# LipSync_Pressure_Board.net
KiCad netlist of a schematic drawn in EAGLE
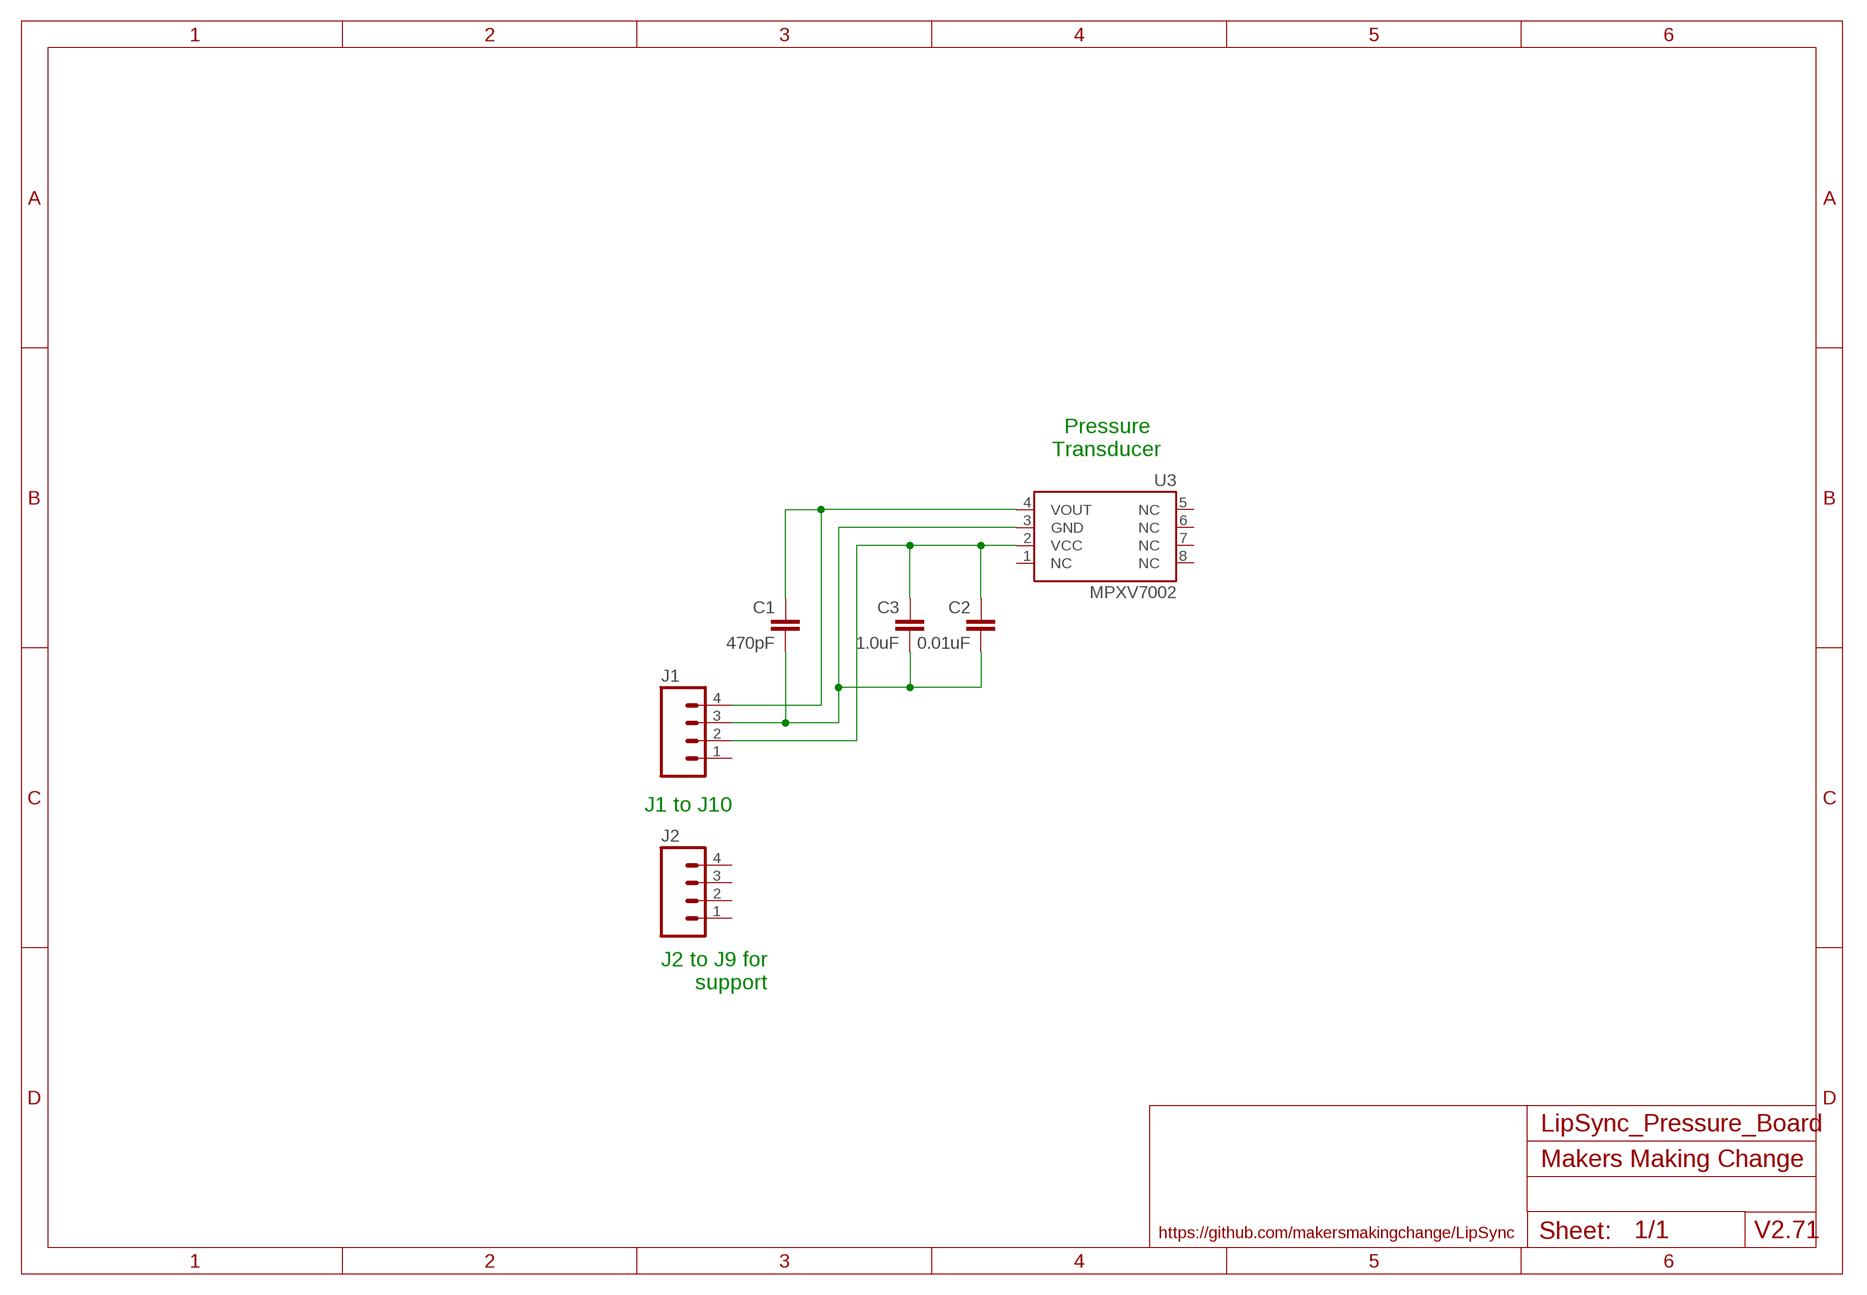
[diagram p0: schematic, sheet 1]

(export (version "E")
  (design (tool "Eeschema 10.0.6"))
  (components
    (comp (ref "C1")
      (value "470pF")
      (footprint "eagle-import:CAP-PTH-SMALLEZ")
      (libsource (lib "eagle-import") (part "CAPEZ"))
    )
    (comp (ref "C2")
      (value "0.01uF")
      (footprint "eagle-import:CAP-PTH-SMALLEZ")
      (libsource (lib "eagle-import") (part "CAPEZ"))
    )
    (comp (ref "C3")
      (value "1.0uF")
      (footprint "eagle-import:CAP-PTH-SMALLEZ")
      (libsource (lib "eagle-import") (part "CAPEZ"))
    )
    (comp (ref "J1")
      (value "M04PTH")
      (footprint "eagle-import:1X04")
      (libsource (lib "eagle-import") (part "M04PTH"))
    )
    (comp (ref "J2")
      (value "M04PTH")
      (footprint "eagle-import:1X04")
      (libsource (lib "eagle-import") (part "M04PTH"))
    )
    (comp (ref "U3")
      (value "MPXV7002")
      (footprint "eagle-import:SOP8")
      (libsource (lib "eagle-import") (part "MPXV7002"))
    )
  )
  (nets
    (net (code "1") (name "Net-(U3-GND)") (class "Default")
      (node (ref "C1") (pin "2") (pinfunction "2_2") (pintype "passive"))
      (node (ref "C2") (pin "2") (pinfunction "2_2") (pintype "passive"))
      (node (ref "C3") (pin "2") (pinfunction "2_2") (pintype "passive"))
      (node (ref "J1") (pin "3") (pinfunction "3_3") (pintype "passive"))
      (node (ref "U3") (pin "3") (pinfunction "GND_3") (pintype "power_in"))
    )
    (net (code "2") (name "Net-(U3-VCC)") (class "Default")
      (node (ref "C2") (pin "1") (pinfunction "1_1") (pintype "passive"))
      (node (ref "C3") (pin "1") (pinfunction "1_1") (pintype "passive"))
      (node (ref "J1") (pin "2") (pinfunction "2_2") (pintype "passive"))
      (node (ref "U3") (pin "2") (pinfunction "VCC_2") (pintype "power_in"))
    )
    (net (code "3") (name "Net-(U3-VOUT)") (class "Default")
      (node (ref "C1") (pin "1") (pinfunction "1_1") (pintype "passive"))
      (node (ref "J1") (pin "4") (pinfunction "4_4") (pintype "passive"))
      (node (ref "U3") (pin "4") (pinfunction "VOUT_4") (pintype "output"))
    )
    (net (code "4") (name "unconnected-(J1-Pad1)") (class "Default")
      (node (ref "J1") (pin "1") (pinfunction "1_1") (pintype "passive"))
    )
    (net (code "5") (name "unconnected-(J2-Pad1)") (class "Default")
      (node (ref "J2") (pin "1") (pinfunction "1_1") (pintype "passive"))
    )
    (net (code "6") (name "unconnected-(J2-Pad2)") (class "Default")
      (node (ref "J2") (pin "2") (pinfunction "2_2") (pintype "passive"))
    )
    (net (code "7") (name "unconnected-(J2-Pad3)") (class "Default")
      (node (ref "J2") (pin "3") (pinfunction "3_3") (pintype "passive"))
    )
    (net (code "8") (name "unconnected-(J2-Pad4)") (class "Default")
      (node (ref "J2") (pin "4") (pinfunction "4_4") (pintype "passive"))
    )
    (net (code "9") (name "unconnected-(U3-NC-Pad1)") (class "Default")
      (node (ref "U3") (pin "1") (pinfunction "NC_1") (pintype "no_connect"))
    )
    (net (code "10") (name "unconnected-(U3-NC-Pad5)") (class "Default")
      (node (ref "U3") (pin "5") (pinfunction "NC_5") (pintype "no_connect"))
    )
    (net (code "11") (name "unconnected-(U3-NC-Pad6)") (class "Default")
      (node (ref "U3") (pin "6") (pinfunction "NC_6") (pintype "no_connect"))
    )
    (net (code "12") (name "unconnected-(U3-NC-Pad7)") (class "Default")
      (node (ref "U3") (pin "7") (pinfunction "NC_7") (pintype "no_connect"))
    )
    (net (code "13") (name "unconnected-(U3-NC-Pad8)") (class "Default")
      (node (ref "U3") (pin "8") (pinfunction "NC_8") (pintype "no_connect"))
    )
  )
)
